# AT86RF231_-_Low_Power_2_4_GHz_Zigbee_802.net
KiCad netlist of a schematic drawn in Altium Designer
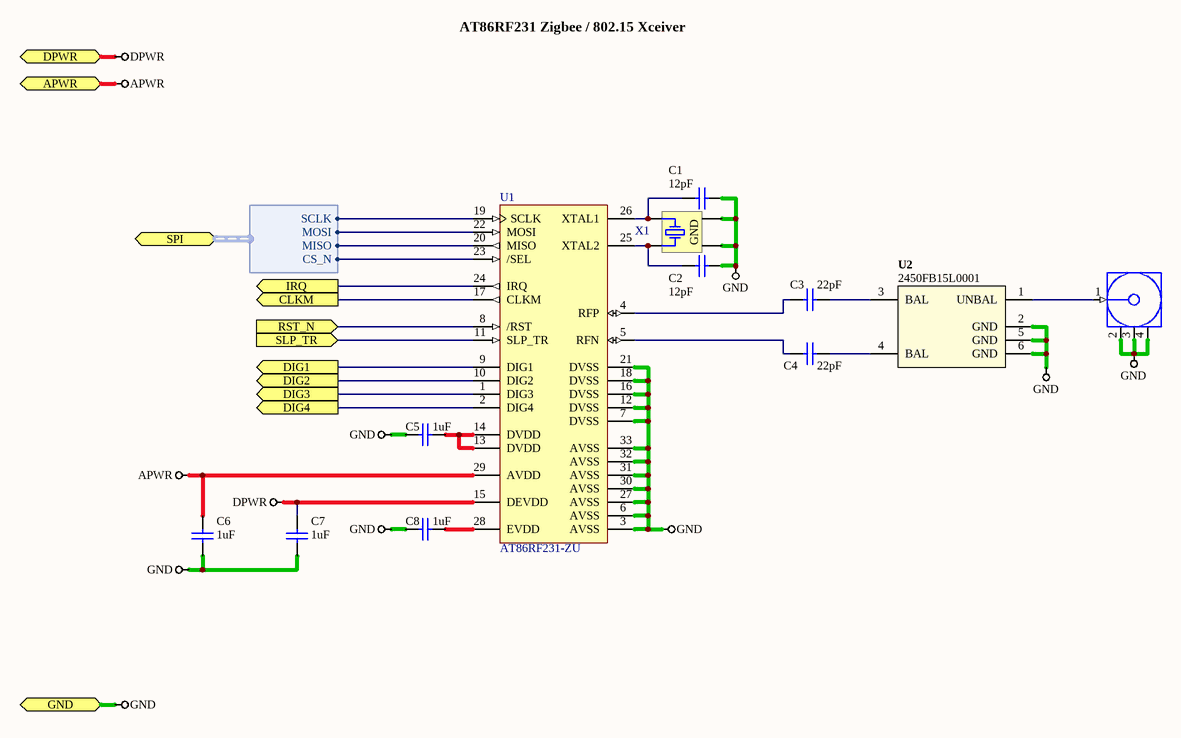
[diagram p0: AT86RF231 - Low Power 2.4 GHz Zigbee 802.15.4 6 LoWPAN Transceiver.SchDoc]

(export (version "E")
  (design (tool "Eeschema 10.0.6"))
  (components
    (comp (ref "C1")
      (value "12pF")
      (footprint "CAPC0402(1005)60_N")
      (description "CAP 12pF 50V ±1% 0402 (1005 Metric) Thickness 0.6mm SMD")
      (fields (field (name "TOLERANCE") "±1%") (field (name "Comment") "CAP 12pF 50V 0402(1005)"))
      (libsource (lib "Altium Vault") (part "CMP-1034-00767-1"))
    )
    (comp (ref "C2")
      (value "12pF")
      (footprint "CAPC0402(1005)60_N")
      (description "CAP 12pF 50V ±1% 0402 (1005 Metric) Thickness 0.6mm SMD")
      (fields (field (name "TOLERANCE") "±1%") (field (name "Comment") "CAP 12pF 50V 0402(1005)"))
      (libsource (lib "Altium Vault") (part "CMP-1034-00767-1"))
    )
    (comp (ref "C3")
      (value "22pF")
      (footprint "CAPC0402(1005)60_N")
      (description "CAP 22pF 50V ±1% 0402 (1005 Metric) Thickness 0.6mm SMD")
      (fields (field (name "TOLERANCE") "±1%") (field (name "Comment") "CAP 22pF 50V 0402(1005)"))
      (libsource (lib "Altium Vault") (part "CMP-1034-00914-1"))
    )
    (comp (ref "C4")
      (value "22pF")
      (footprint "CAPC0402(1005)60_N")
      (description "CAP 22pF 50V ±1% 0402 (1005 Metric) Thickness 0.6mm SMD")
      (fields (field (name "TOLERANCE") "±1%") (field (name "Comment") "CAP 22pF 50V 0402(1005)"))
      (libsource (lib "Altium Vault") (part "CMP-1034-00914-1"))
    )
    (comp (ref "C5")
      (value "1uF")
      (footprint "CAPC0402(1005)60_N")
      (description "CAP 1uF 16V ±10% 0402 (1005 Metric) Thickness 0.6mm SMD")
      (fields (field (name "TOLERANCE") "±10%") (field (name "Comment") "CAP 1uF 16V 0402(1005)"))
      (libsource (lib "Altium Vault") (part "CMP-1034-02119-1"))
    )
    (comp (ref "C6")
      (value "1uF")
      (footprint "CAPC0402(1005)60_N")
      (description "CAP 1uF 16V ±10% 0402 (1005 Metric) Thickness 0.6mm SMD")
      (fields (field (name "TOLERANCE") "±10%") (field (name "Comment") "CAP 1uF 16V 0402(1005)"))
      (libsource (lib "Altium Content Vault") (part "CMP-1034-02119-1"))
    )
    (comp (ref "C7")
      (value "1uF")
      (footprint "CAPC0402(1005)60_N")
      (description "CAP 1uF 16V ±10% 0402 (1005 Metric) Thickness 0.6mm SMD")
      (fields (field (name "TOLERANCE") "±10%") (field (name "Comment") "CAP 1uF 16V 0402(1005)"))
      (libsource (lib "Altium Vault") (part "CMP-1034-02119-1"))
    )
    (comp (ref "C8")
      (value "1uF")
      (footprint "CAPC0402(1005)60_N")
      (description "CAP 1uF 16V ±10% 0402 (1005 Metric) Thickness 0.6mm SMD")
      (fields (field (name "TOLERANCE") "±10%") (field (name "Comment") "CAP 1uF 16V 0402(1005)"))
      (libsource (lib "Altium Vault") (part "CMP-1034-02119-1"))
    )
    (comp (ref "J*")
      (value "MOLX-73412-0110")
      (footprint "MOLX-73412-0110")
      (libsource (lib "Component_Database") (part "MOLX-73412-0110"))
    )
    (comp (ref "U1")
      (value "AT86RF231-ZU")
      (footprint "32QN2_L")
      (libsource (lib "Altium Content Vault") (part "CMP-0107-00028-2"))
    )
    (comp (ref "U2")
      (value "2450FB15L0001")
      (footprint "JOHT-BALUN200X125X90-6")
      (description "Filter Balun Atmel 2.45GHZ")
      (libsource (lib "Altium Vault") (part "CMP-5152-00000-1"))
    )
    (comp (ref "X1")
      (value "S-4025")
      (fields (field (name "MANUFACTURER") "SIWARD"))
      (libsource (lib "SIWARD - S4025") (part "S-4025"))
    )
  )
  (nets
    (net (code "2") (name "/CLKM") (class "Default")
      (node (ref "U1") (pin "17") (pinfunction "CLKM_17") (pintype "output"))
    )
    (net (code "3") (name "/CS_N") (class "Default")
      (node (ref "U1") (pin "23") (pinfunction "/SEL_23") (pintype "input"))
    )
    (net (code "4") (name "/DIG1") (class "Default")
      (node (ref "U1") (pin "9") (pinfunction "DIG1_9") (pintype "passive"))
    )
    (net (code "5") (name "/DIG2") (class "Default")
      (node (ref "U1") (pin "10") (pinfunction "DIG2_10") (pintype "passive"))
    )
    (net (code "6") (name "/DIG3") (class "Default")
      (node (ref "U1") (pin "1") (pinfunction "DIG3_1") (pintype "passive"))
    )
    (net (code "7") (name "/DIG4") (class "Default")
      (node (ref "U1") (pin "2") (pinfunction "DIG4_2") (pintype "passive"))
    )
    (net (code "8") (name "/IRQ") (class "Default")
      (node (ref "U1") (pin "24") (pinfunction "IRQ_24") (pintype "output"))
    )
    (net (code "9") (name "/MISO") (class "Default")
      (node (ref "U1") (pin "20") (pinfunction "MISO_20") (pintype "output"))
    )
    (net (code "10") (name "/MOSI") (class "Default")
      (node (ref "U1") (pin "22") (pinfunction "MOSI_22") (pintype "input"))
    )
    (net (code "11") (name "/RST_N") (class "Default")
      (node (ref "U1") (pin "8") (pinfunction "/RST_8") (pintype "input"))
    )
    (net (code "12") (name "/SCLK") (class "Default")
      (node (ref "U1") (pin "19") (pinfunction "SCLK_19") (pintype "input"))
    )
    (net (code "13") (name "/SLP_TR") (class "Default")
      (node (ref "U1") (pin "11") (pinfunction "SLP_TR_11") (pintype "input"))
    )
    (net (code "15") (name "APWR") (class "Default")
      (node (ref "C6") (pin "2") (pinfunction "2_2") (pintype "passive"))
      (node (ref "U1") (pin "29") (pinfunction "AVDD_29") (pintype "power_in"))
    )
    (net (code "16") (name "DPWR") (class "Default")
      (node (ref "C7") (pin "2") (pinfunction "2_2") (pintype "passive"))
      (node (ref "U1") (pin "15") (pinfunction "DEVDD_15") (pintype "power_in"))
    )
    (net (code "17") (name "GND") (class "Default")
      (node (ref "C1") (pin "1") (pinfunction "1_1") (pintype "passive"))
      (node (ref "C2") (pin "1") (pinfunction "1_1") (pintype "passive"))
      (node (ref "C5") (pin "2") (pinfunction "2_2") (pintype "passive"))
      (node (ref "C6") (pin "1") (pinfunction "1_1") (pintype "passive"))
      (node (ref "C7") (pin "1") (pinfunction "1_1") (pintype "passive"))
      (node (ref "C8") (pin "2") (pinfunction "2_2") (pintype "passive"))
      (node (ref "J*") (pin "2") (pinfunction "GND_2") (pintype "power_in"))
      (node (ref "J*") (pin "3") (pinfunction "GND_3") (pintype "power_in"))
      (node (ref "J*") (pin "4") (pinfunction "GND_4") (pintype "power_in"))
      (node (ref "U1") (pin "12") (pinfunction "DVSS_12") (pintype "power_in"))
      (node (ref "U1") (pin "16") (pinfunction "DVSS_16") (pintype "power_in"))
      (node (ref "U1") (pin "18") (pinfunction "DVSS_18") (pintype "power_in"))
      (node (ref "U1") (pin "21") (pinfunction "DVSS_21") (pintype "power_in"))
      (node (ref "U1") (pin "27") (pinfunction "AVSS_27") (pintype "power_in"))
      (node (ref "U1") (pin "3") (pinfunction "AVSS_3") (pintype "power_in"))
      (node (ref "U1") (pin "30") (pinfunction "AVSS_30") (pintype "power_in"))
      (node (ref "U1") (pin "31") (pinfunction "AVSS_31") (pintype "power_in"))
      (node (ref "U1") (pin "32") (pinfunction "AVSS_32") (pintype "power_in"))
      (node (ref "U1") (pin "33") (pinfunction "AVSS_33") (pintype "power_in"))
      (node (ref "U1") (pin "6") (pinfunction "AVSS_6") (pintype "power_in"))
      (node (ref "U1") (pin "7") (pinfunction "DVSS_7") (pintype "power_in"))
      (node (ref "U2") (pin "2") (pinfunction "GND_2") (pintype "power_in"))
      (node (ref "U2") (pin "5") (pinfunction "GND_5") (pintype "power_in"))
      (node (ref "U2") (pin "6") (pinfunction "GND_6") (pintype "power_in"))
      (node (ref "X1") (pin "2") (pinfunction "GND_2") (pintype "power_in"))
      (node (ref "X1") (pin "4") (pinfunction "GND_4") (pintype "power_in"))
    )
    (net (code "18") (name "Net-(C3-Pad2)") (class "Default")
      (node (ref "C3") (pin "2") (pinfunction "2_2") (pintype "passive"))
      (node (ref "U2") (pin "3") (pinfunction "BAL_3") (pintype "passive"))
    )
    (net (code "19") (name "Net-(C4-Pad2)") (class "Default")
      (node (ref "C4") (pin "2") (pinfunction "2_2") (pintype "passive"))
      (node (ref "U2") (pin "4") (pinfunction "BAL_4") (pintype "passive"))
    )
    (net (code "20") (name "Net-(C5-Pad1)") (class "Default")
      (node (ref "C5") (pin "1") (pinfunction "1_1") (pintype "passive"))
      (node (ref "U1") (pin "13") (pinfunction "DVDD_13") (pintype "power_in"))
      (node (ref "U1") (pin "14") (pinfunction "DVDD_14") (pintype "power_in"))
    )
    (net (code "21") (name "Net-(J*-Signal)") (class "Default")
      (node (ref "J*") (pin "1") (pinfunction "Signal_1") (pintype "input"))
      (node (ref "U2") (pin "1") (pinfunction "UNBAL_1") (pintype "passive"))
    )
    (net (code "22") (name "Net-(U1-EVDD)") (class "Default")
      (node (ref "C8") (pin "1") (pinfunction "1_1") (pintype "passive"))
      (node (ref "U1") (pin "28") (pinfunction "EVDD_28") (pintype "power_in"))
    )
    (net (code "23") (name "Net-(U1-RFN)") (class "Default")
      (node (ref "C4") (pin "1") (pinfunction "1_1") (pintype "passive"))
      (node (ref "U1") (pin "5") (pinfunction "RFN_5") (pintype "bidirectional"))
    )
    (net (code "24") (name "Net-(U1-RFP)") (class "Default")
      (node (ref "C3") (pin "1") (pinfunction "1_1") (pintype "passive"))
      (node (ref "U1") (pin "4") (pinfunction "RFP_4") (pintype "bidirectional"))
    )
    (net (code "25") (name "Net-(U1-XTAL1)") (class "Default")
      (node (ref "C1") (pin "2") (pinfunction "2_2") (pintype "passive"))
      (node (ref "U1") (pin "26") (pinfunction "XTAL1_26") (pintype "passive"))
      (node (ref "X1") (pin "1") (pinfunction "X1_1") (pintype "passive"))
    )
    (net (code "26") (name "Net-(U1-XTAL2)") (class "Default")
      (node (ref "C2") (pin "2") (pinfunction "2_2") (pintype "passive"))
      (node (ref "U1") (pin "25") (pinfunction "XTAL2_25") (pintype "passive"))
      (node (ref "X1") (pin "3") (pinfunction "X2_3") (pintype "passive"))
    )
  )
)
